# SRIC_Peripherals.net
KiCad netlist of a schematic drawn in Altium Designer
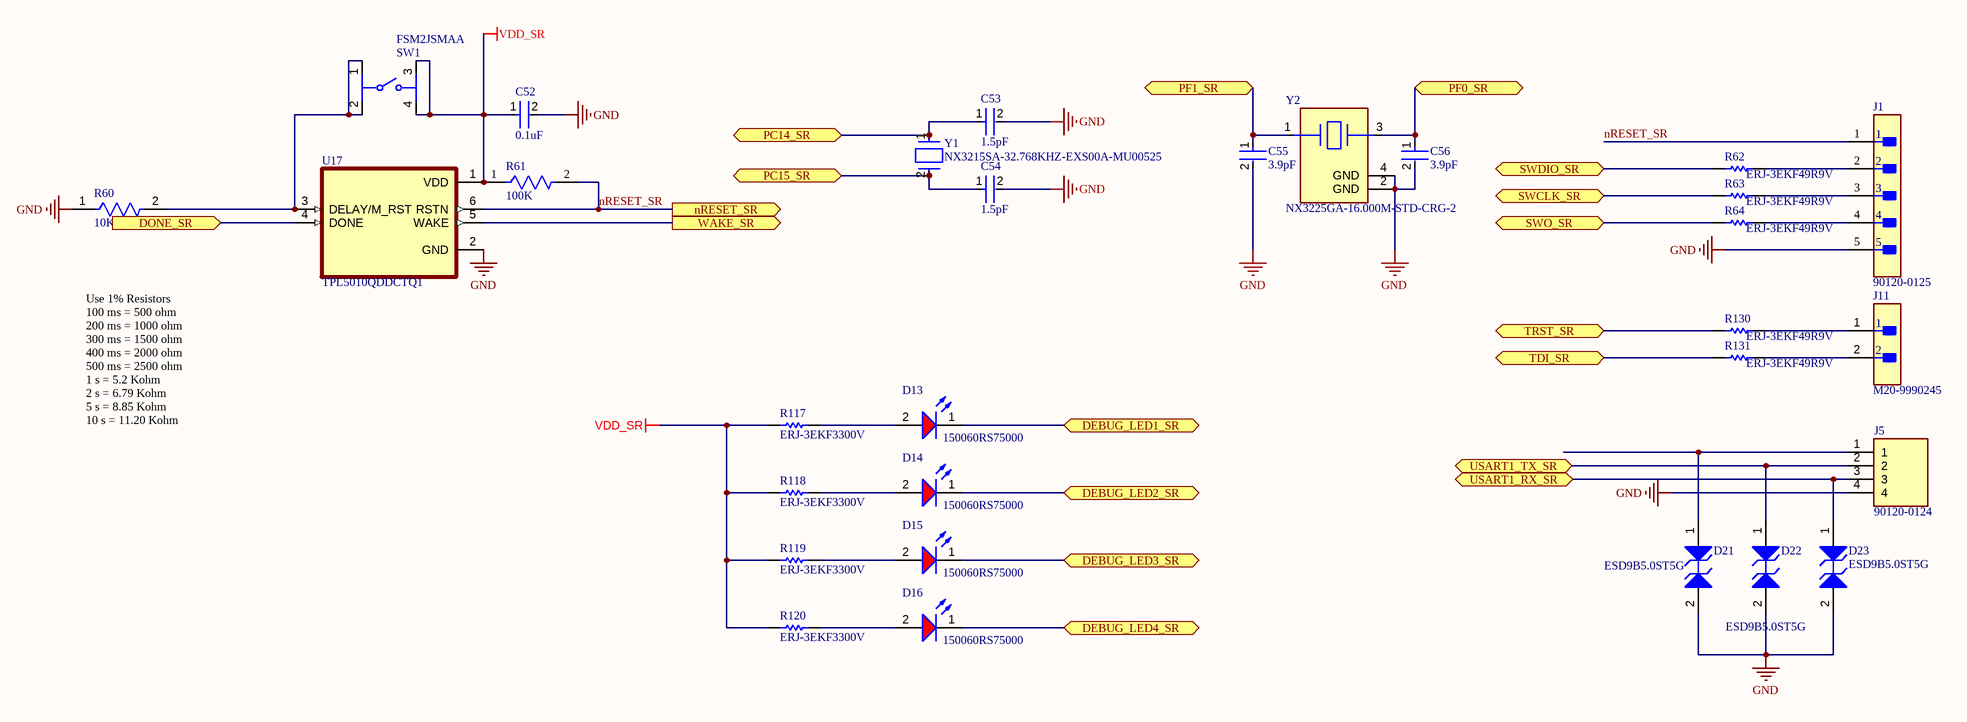
[diagram p0: SRIC_Peripherals.SchDoc]

(export (version "E")
  (design (tool "Eeschema 10.0.6"))
  (components
    (comp (ref "C52")
      (value "0.1uF")
      (footprint "FP-C0603C-CF-MFG")
      (description "CAP CER 0.1UF 50V X7R 0603")
      (fields (field (name "TOLERANCE") "0.1") (field (name "MANUFACTURER") "KEMET"))
      (libsource (lib "Altium Content Vault") (part "b4654b650e69147ec39a6b967a45e02"))
    )
    (comp (ref "C53")
      (value "1.5pF")
      (footprint "FP-C0603C-CF-MFG")
      (description "CAP CER 1.5PF 100V NP0 0603")
      (fields
        (field (name "MANUFACTURER PART NUMBER") "C0603C159C1GACTU")
        (field (name "TOLERANCE") "0.25 pF")
      )
      (libsource (lib "Altium Content Vault") (part "b4654b650e69147ec39a6b967a45e02"))
    )
    (comp (ref "C54")
      (value "1.5pF")
      (footprint "FP-C0603C-CF-MFG")
      (description "CAP CER 1.5PF 100V NP0 0603")
      (fields
        (field (name "MANUFACTURER PART NUMBER") "C0603C159C1GACTU")
        (field (name "TOLERANCE") "0.25 pF")
      )
      (libsource (lib "Altium Content Vault") (part "b4654b650e69147ec39a6b967a45e02"))
    )
    (comp (ref "C55")
      (value "3.9pF")
      (footprint "FP-CBR06C-MFG")
      (description "CAP CER 3.9PF 250V C0G/NP0 0603")
      (fields
        (field (name "OCTOPART") "https://octopart.com/cbr06c399cagac-kemet-20446767")
        (field (name "MANUFACTURER PART NUMBER") "CBR06C399CAGAC")
      )
      (libsource (lib "Altium Content Vault") (part "11868f565c42a9108669ba33697ecf6"))
    )
    (comp (ref "C56")
      (value "3.9pF")
      (footprint "FP-CBR06C-MFG")
      (description "CAP CER 3.9PF 250V C0G/NP0 0603")
      (fields
        (field (name "OCTOPART") "https://octopart.com/cbr06c399cagac-kemet-20446767")
        (field (name "MANUFACTURER PART NUMBER") "CBR06C399CAGAC")
      )
      (libsource (lib "Altium Content Vault") (part "11868f565c42a9108669ba33697ecf6"))
    )
    (comp (ref "D13")
      (value "150060RS75000")
      (footprint "WL-SMCW_0603_150060xx75000")
      (description "LED Low-Power Uni-Color Red 630nm 2V 2-Pin Chip 0603(1608Metric) T/R")
      (libsource (lib "Altium Content Vault") (part "LED_Red_2A-1K"))
    )
    (comp (ref "D14")
      (value "150060RS75000")
      (footprint "WL-SMCW_0603_150060xx75000")
      (description "LED Low-Power Uni-Color Red 630nm 2V 2-Pin Chip 0603(1608Metric) T/R")
      (libsource (lib "Altium Content Vault") (part "LED_Red_2A-1K"))
    )
    (comp (ref "D15")
      (value "150060RS75000")
      (footprint "WL-SMCW_0603_150060xx75000")
      (description "LED Low-Power Uni-Color Red 630nm 2V 2-Pin Chip 0603(1608Metric) T/R")
      (libsource (lib "Altium Content Vault") (part "LED_Red_2A-1K"))
    )
    (comp (ref "D16")
      (value "150060RS75000")
      (footprint "WL-SMCW_0603_150060xx75000")
      (description "LED Low-Power Uni-Color Red 630nm 2V 2-Pin Chip 0603(1608Metric) T/R")
      (libsource (lib "Altium Content Vault") (part "LED_Red_2A-1K"))
    )
    (comp (ref "D21")
      (value "ESD9B5.0ST5G")
      (footprint "ONSC-SOD-923-2-514AB-01_V")
      (fields (field (name "MANUFACTURER") "On Semiconductor"))
      (libsource (lib "Altium Content Vault") (part "ONSC-A1A2-2"))
    )
    (comp (ref "D22")
      (value "ESD9B5.0ST5G")
      (footprint "ONSC-SOD-923-2-514AB-01_V")
      (fields (field (name "MANUFACTURER") "On Semiconductor"))
      (libsource (lib "Altium Content Vault") (part "ONSC-A1A2-2"))
    )
    (comp (ref "D23")
      (value "ESD9B5.0ST5G")
      (footprint "ONSC-SOD-923-2-514AB-01_V")
      (fields (field (name "MANUFACTURER") "On Semiconductor"))
      (libsource (lib "Altium Content Vault") (part "ONSC-A1A2-2"))
    )
    (comp (ref "J1")
      (value "90120-0125")
      (footprint "FP-90120-0125-MFG")
      (description "90120-0125 2.54mm Pitch C-Grid III Header, Single Row, Vertical, 5 Circuits, Tin (Sn) Plating")
      (libsource (lib "Altium Content Vault") (part "bf93c07fd2649a848d0ec8585582aab"))
    )
    (comp (ref "J5")
      (value "90120-0124")
      (footprint "SamacSys:HDRV4W65P0X254_1X4_1016X254X945P")
      (description "Connector")
      (fields (field (name "MOUSER PART NUMBER") "538-90120-0124"))
      (libsource (lib "*") (part "90120-0124"))
    )
    (comp (ref "J11")
      (value "M20-9990245")
      (footprint "FP-M20-9990245-MFG")
      (description "CONN HEADER VERT 2POS 2.54MM")
      (fields (field (name "VOLTAGE") "50V"))
      (libsource (lib "Altium Content Vault") (part "3bc925449376181038e59eaffc5286c"))
    )
    (comp (ref "R60")
      (value "10K")
      (footprint "FP-RK73B1J-MFG")
      (description "RES 10K OHM 5% 1/10W 0603")
      (fields (field (name "TOLERANCE") "5%"))
      (libsource (lib "Altium Content Vault") (part "1029c3af85768c4190bb7ad29bc67b5"))
    )
    (comp (ref "R61")
      (value "100K")
      (footprint "FP-ERA3A-MFG")
      (fields (field (name "TOLERANCE") "0.1%"))
      (libsource (lib "Altium Content Vault") (part "1029c3af85768c4190bb7ad29bc67b5"))
    )
    (comp (ref "R62")
      (value "ERJ-3EKF49R9V")
      (footprint "RESC1608X55X30ML15T15")
      (fields (field (name "MANUFACTURER") "Panasonic"))
      (libsource (lib "Altium Content Vault") (part "RES"))
    )
    (comp (ref "R63")
      (value "ERJ-3EKF49R9V")
      (footprint "RESC1608X55X30ML15T15")
      (fields (field (name "MANUFACTURER") "Panasonic"))
      (libsource (lib "Altium Content Vault") (part "RES"))
    )
    (comp (ref "R64")
      (value "ERJ-3EKF49R9V")
      (footprint "RESC1608X55X30ML15T15")
      (fields (field (name "MANUFACTURER") "Panasonic"))
      (libsource (lib "Altium Content Vault") (part "RES"))
    )
    (comp (ref "R117")
      (value "ERJ-3EKF3300V")
      (footprint "RESC1608X55X30LL15T15")
      (description "Chip Resistor, 330 Ohm, +/- 1%, 0.1 W, -55 to 155 degC, 0603 (1608 Metric), RoHS, Tape and Reel")
      (libsource (lib "Altium Content Vault") (part "RES-2"))
    )
    (comp (ref "R118")
      (value "ERJ-3EKF3300V")
      (footprint "RESC1608X55X30LL15T15")
      (description "Chip Resistor, 330 Ohm, +/- 1%, 0.1 W, -55 to 155 degC, 0603 (1608 Metric), RoHS, Tape and Reel")
      (libsource (lib "Altium Content Vault") (part "RES-2"))
    )
    (comp (ref "R119")
      (value "ERJ-3EKF3300V")
      (footprint "RESC1608X55X30LL15T15")
      (description "Chip Resistor, 330 Ohm, +/- 1%, 0.1 W, -55 to 155 degC, 0603 (1608 Metric), RoHS, Tape and Reel")
      (libsource (lib "Altium Content Vault") (part "RES-2"))
    )
    (comp (ref "R120")
      (value "ERJ-3EKF3300V")
      (footprint "RESC1608X55X30LL15T15")
      (description "Chip Resistor, 330 Ohm, +/- 1%, 0.1 W, -55 to 155 degC, 0603 (1608 Metric), RoHS, Tape and Reel")
      (libsource (lib "Altium Content Vault") (part "RES-2"))
    )
    (comp (ref "R130")
      (value "ERJ-3EKF49R9V")
      (footprint "RESC1608X55X30ML15T15")
      (fields (field (name "MANUFACTURER") "Panasonic"))
      (libsource (lib "Altium Content Vault") (part "RES"))
    )
    (comp (ref "R131")
      (value "ERJ-3EKF49R9V")
      (footprint "RESC1608X55X30ML15T15")
      (fields (field (name "MANUFACTURER") "Panasonic"))
      (libsource (lib "Altium Content Vault") (part "RES"))
    )
    (comp (ref "SW1")
      (value "FSM2JSMAA")
      (footprint "FP-FSM2JSMAA-MFG")
      (description "SWITCH TACTILE SPST-NO 0.05A 24V")
      (fields
        (field (name "MANUFACTURER") "TE Connectivity")
        (field (name "OCTOPART") "https://octopart.com/fsm2jsmaa-te+connectivity-41720620")
      )
      (libsource (lib "Altium Content Vault") (part "b8895f3f4cefb76e1819d2863dba89b"))
    )
    (comp (ref "U17")
      (value "TPL5010QDDCTQ1")
      (footprint "SOT95P280X110-6N")
      (description "Automotive AEC-Q100, nano-powered system timer with watchdog function")
      (fields (field (name "MF") "Texas Instruments"))
      (libsource (lib "Hitesh Bhoyar") (part "TPL5010QDDCTQ1"))
    )
    (comp (ref "Y1")
      (value "NX3215SA-32.768KHZ-EXS00A-MU00525")
      (footprint "FP-NX3215SA-MFG")
      (description "CRYSTAL 32.7680KHZ 6PF SMD")
      (libsource (lib "Altium Content Vault") (part "c23a69dc6c9e2f18f2079038eb95dd1"))
    )
    (comp (ref "Y2")
      (value "NX3225GA-16.000M-STD-CRG-2")
      (footprint "FP-NX3225GA-MFG")
      (description "CRYSTAL 16.0000MHZ 8PF SMD")
      (libsource (lib "Altium Content Vault") (part "6320effb7d3e443b36bf79d8ebe02e5"))
    )
  )
  (nets
    (net (code "1") (name "/DEBUG_LED1_SR") (class "Default")
      (node (ref "D13") (pin "1") (pinfunction "K_1") (pintype "passive"))
    )
    (net (code "2") (name "/DEBUG_LED2_SR") (class "Default")
      (node (ref "D14") (pin "1") (pinfunction "K_1") (pintype "passive"))
    )
    (net (code "3") (name "/DEBUG_LED3_SR") (class "Default")
      (node (ref "D15") (pin "1") (pinfunction "K_1") (pintype "passive"))
    )
    (net (code "4") (name "/DEBUG_LED4_SR") (class "Default")
      (node (ref "D16") (pin "1") (pinfunction "K_1") (pintype "passive"))
    )
    (net (code "5") (name "/DONE_SR") (class "Default")
      (node (ref "U17") (pin "4") (pinfunction "DONE_4") (pintype "input"))
    )
    (net (code "6") (name "/PC14_SR") (class "Default")
      (node (ref "C53") (pin "1") (pinfunction "1_1") (pintype "passive"))
      (node (ref "Y1") (pin "1") (pinfunction "1_1") (pintype "passive"))
    )
    (net (code "7") (name "/PC15_SR") (class "Default")
      (node (ref "C54") (pin "1") (pinfunction "1_1") (pintype "passive"))
      (node (ref "Y1") (pin "2") (pinfunction "2_2") (pintype "passive"))
    )
    (net (code "8") (name "/PF0_SR") (class "Default")
      (node (ref "C56") (pin "1") (pinfunction "1_1") (pintype "passive"))
      (node (ref "Y2") (pin "3") (pinfunction "3_3") (pintype "passive"))
    )
    (net (code "9") (name "/PF1_SR") (class "Default")
      (node (ref "C55") (pin "1") (pinfunction "1_1") (pintype "passive"))
      (node (ref "Y2") (pin "1") (pinfunction "1_1") (pintype "passive"))
    )
    (net (code "10") (name "/SWCLK_SR") (class "Default")
      (node (ref "R63") (pin "1") (pinfunction "1_1") (pintype "passive"))
    )
    (net (code "11") (name "/SWDIO_SR") (class "Default")
      (node (ref "R62") (pin "1") (pinfunction "1_1") (pintype "passive"))
    )
    (net (code "12") (name "/SWO_SR") (class "Default")
      (node (ref "R64") (pin "1") (pinfunction "1_1") (pintype "passive"))
    )
    (net (code "13") (name "/TDI_SR") (class "Default")
      (node (ref "R131") (pin "1") (pinfunction "1_1") (pintype "passive"))
    )
    (net (code "14") (name "/TRST_SR") (class "Default")
      (node (ref "R130") (pin "1") (pinfunction "1_1") (pintype "passive"))
    )
    (net (code "15") (name "/USART1_RX_SR") (class "Default")
      (node (ref "D23") (pin "1") (pinfunction "A1_1") (pintype "passive"))
      (node (ref "J5") (pin "3") (pinfunction "3_3") (pintype "passive"))
    )
    (net (code "16") (name "/USART1_TX_SR") (class "Default")
      (node (ref "D22") (pin "1") (pinfunction "A1_1") (pintype "passive"))
      (node (ref "J5") (pin "2") (pinfunction "2_2") (pintype "passive"))
    )
    (net (code "17") (name "/WAKE_SR") (class "Default")
      (node (ref "U17") (pin "5") (pinfunction "WAKE_5") (pintype "output"))
    )
    (net (code "18") (name "/nRESET_SR") (class "Default")
      (node (ref "J1") (pin "1") (pinfunction "1_1") (pintype "passive"))
      (node (ref "R61") (pin "2") (pinfunction "2_2") (pintype "passive"))
      (node (ref "U17") (pin "6") (pinfunction "RSTN_6") (pintype "output"))
    )
    (net (code "19") (name "GND") (class "Default")
      (node (ref "C52") (pin "2") (pinfunction "2_2") (pintype "passive"))
      (node (ref "C53") (pin "2") (pinfunction "2_2") (pintype "passive"))
      (node (ref "C54") (pin "2") (pinfunction "2_2") (pintype "passive"))
      (node (ref "C55") (pin "2") (pinfunction "2_2") (pintype "passive"))
      (node (ref "C56") (pin "2") (pinfunction "2_2") (pintype "passive"))
      (node (ref "D21") (pin "2") (pinfunction "A2_2") (pintype "passive"))
      (node (ref "D22") (pin "2") (pinfunction "A2_2") (pintype "passive"))
      (node (ref "D23") (pin "2") (pinfunction "A2_2") (pintype "passive"))
      (node (ref "J1") (pin "5") (pinfunction "5_5") (pintype "passive"))
      (node (ref "J5") (pin "4") (pinfunction "4_4") (pintype "passive"))
      (node (ref "R60") (pin "1") (pinfunction "1_1") (pintype "passive"))
      (node (ref "U17") (pin "2") (pinfunction "GND_2") (pintype "power_in"))
      (node (ref "Y2") (pin "2") (pinfunction "GND_2") (pintype "power_in"))
      (node (ref "Y2") (pin "4") (pinfunction "GND_4") (pintype "power_in"))
    )
    (net (code "20") (name "Net-(D13-A)") (class "Default")
      (node (ref "D13") (pin "2") (pinfunction "A_2") (pintype "passive"))
      (node (ref "R117") (pin "2") (pinfunction "2_2") (pintype "passive"))
    )
    (net (code "21") (name "Net-(D14-A)") (class "Default")
      (node (ref "D14") (pin "2") (pinfunction "A_2") (pintype "passive"))
      (node (ref "R118") (pin "2") (pinfunction "2_2") (pintype "passive"))
    )
    (net (code "22") (name "Net-(D15-A)") (class "Default")
      (node (ref "D15") (pin "2") (pinfunction "A_2") (pintype "passive"))
      (node (ref "R119") (pin "2") (pinfunction "2_2") (pintype "passive"))
    )
    (net (code "23") (name "Net-(D16-A)") (class "Default")
      (node (ref "D16") (pin "2") (pinfunction "A_2") (pintype "passive"))
      (node (ref "R120") (pin "2") (pinfunction "2_2") (pintype "passive"))
    )
    (net (code "24") (name "Net-(D21-A1)") (class "Default")
      (node (ref "D21") (pin "1") (pinfunction "A1_1") (pintype "passive"))
      (node (ref "J5") (pin "1") (pinfunction "1_1") (pintype "passive"))
    )
    (net (code "25") (name "Net-(J1-Pad2)") (class "Default")
      (node (ref "J1") (pin "2") (pinfunction "2_2") (pintype "passive"))
      (node (ref "R62") (pin "2") (pinfunction "2_2") (pintype "passive"))
    )
    (net (code "26") (name "Net-(J1-Pad3)") (class "Default")
      (node (ref "J1") (pin "3") (pinfunction "3_3") (pintype "passive"))
      (node (ref "R63") (pin "2") (pinfunction "2_2") (pintype "passive"))
    )
    (net (code "27") (name "Net-(J1-Pad4)") (class "Default")
      (node (ref "J1") (pin "4") (pinfunction "4_4") (pintype "passive"))
      (node (ref "R64") (pin "2") (pinfunction "2_2") (pintype "passive"))
    )
    (net (code "28") (name "Net-(J11-Pad1)") (class "Default")
      (node (ref "J11") (pin "1") (pinfunction "1_1") (pintype "passive"))
      (node (ref "R130") (pin "2") (pinfunction "2_2") (pintype "passive"))
    )
    (net (code "29") (name "Net-(J11-Pad2)") (class "Default")
      (node (ref "J11") (pin "2") (pinfunction "2_2") (pintype "passive"))
      (node (ref "R131") (pin "2") (pinfunction "2_2") (pintype "passive"))
    )
    (net (code "30") (name "Net-(U17-DELAY{slash}M_RST)") (class "Default")
      (node (ref "R60") (pin "2") (pinfunction "2_2") (pintype "passive"))
      (node (ref "SW1") (pin "1") (pinfunction "1_1") (pintype "passive"))
      (node (ref "SW1") (pin "2") (pinfunction "2_2") (pintype "passive"))
      (node (ref "U17") (pin "3") (pinfunction "DELAY/M_RST_3") (pintype "input"))
    )
    (net (code "31") (name "VDD_SR") (class "Default")
      (node (ref "C52") (pin "1") (pinfunction "1_1") (pintype "passive"))
      (node (ref "R117") (pin "1") (pinfunction "1_1") (pintype "passive"))
      (node (ref "R118") (pin "1") (pinfunction "1_1") (pintype "passive"))
      (node (ref "R119") (pin "1") (pinfunction "1_1") (pintype "passive"))
      (node (ref "R120") (pin "1") (pinfunction "1_1") (pintype "passive"))
      (node (ref "R61") (pin "1") (pinfunction "1_1") (pintype "passive"))
      (node (ref "SW1") (pin "3") (pinfunction "3_3") (pintype "passive"))
      (node (ref "SW1") (pin "4") (pinfunction "4_4") (pintype "passive"))
      (node (ref "U17") (pin "1") (pinfunction "VDD_1") (pintype "power_in"))
    )
  )
)
